# LasCon.net
KiCad netlist of a schematic drawn in EAGLE
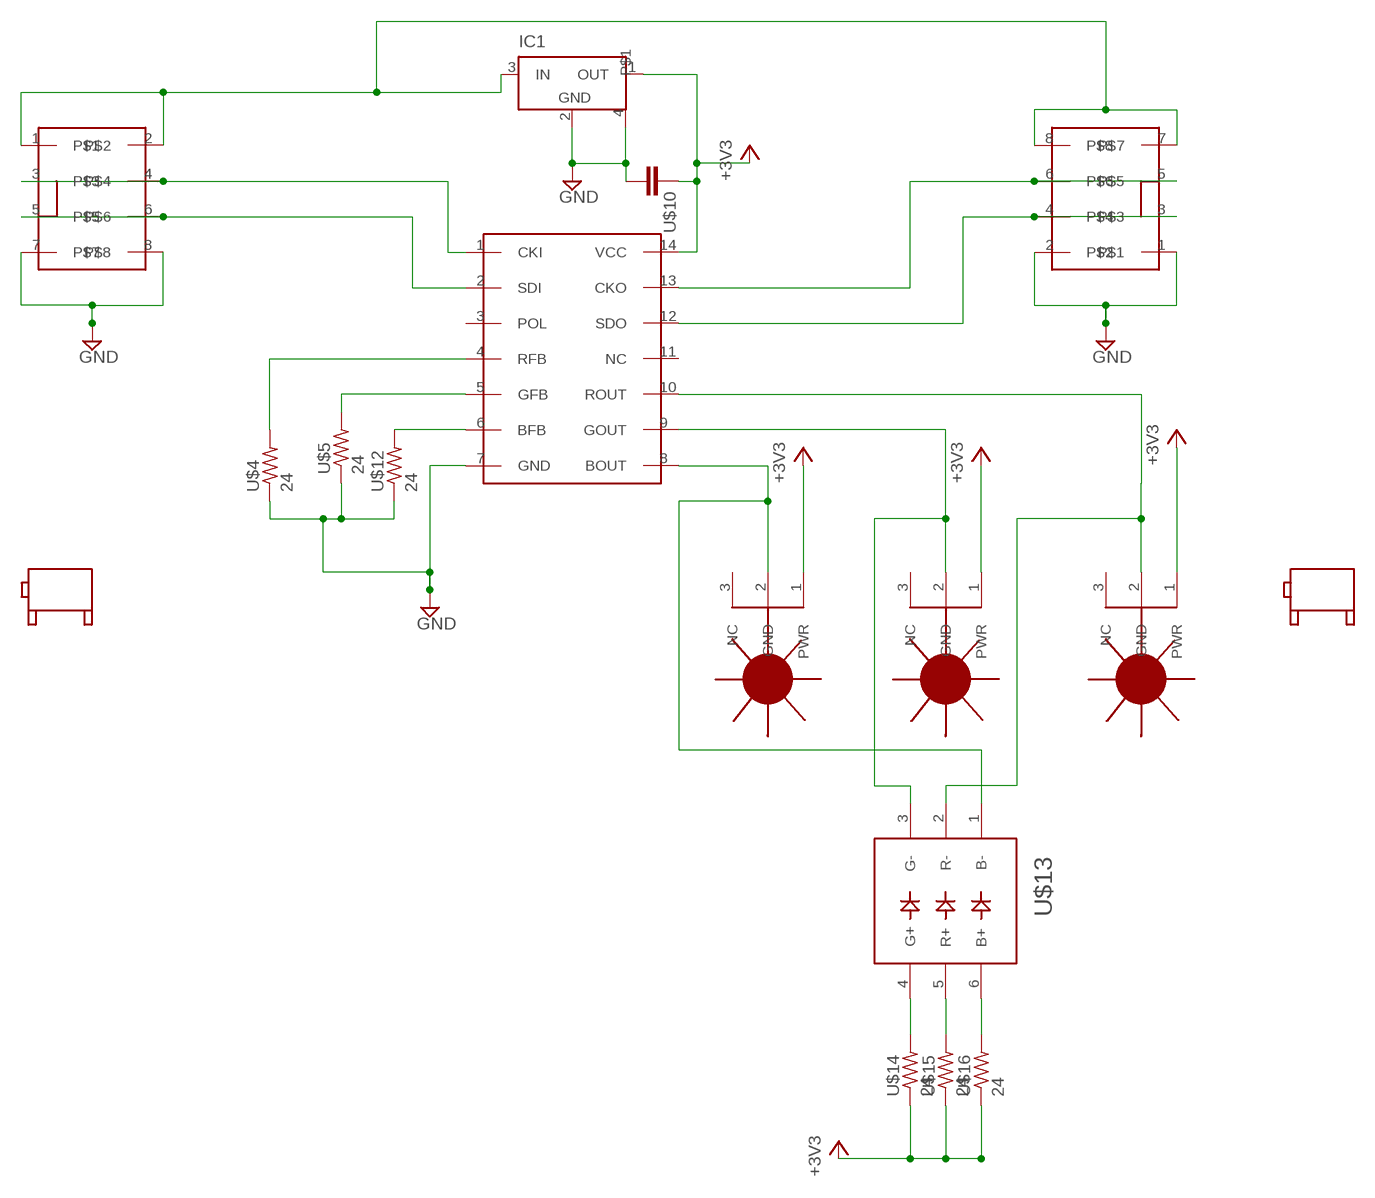
[diagram p0: schematic, sheet 1]

(export (version "E")
  (design (tool "Eeschema 10.0.6"))
  (components
    (comp (ref "IC1")
      (value "MCP1804T-3302I")
      (footprint "eagle-import:SOT223")
      (fields (field (name "MPN") "MCP1804T-3302I/DB"))
      (libsource (lib "eagle-import") (part "MCP1804T-3302I"))
    )
    (comp (ref "U$1")
      (value "2X4IDC")
      (footprint "eagle-import:2X04")
      (fields (field (name "MPN") "75869-132LF"))
      (libsource (lib "eagle-import") (part "2X4IDC"))
    )
    (comp (ref "U$2")
      (value "2X4IDC")
      (footprint "eagle-import:2X04")
      (fields (field (name "MPN") "75869-132LF"))
      (libsource (lib "eagle-import") (part "2X4IDC"))
    )
    (comp (ref "U$3")
      (value "WS2801")
      (footprint "eagle-import:SO14")
      (libsource (lib "eagle-import") (part "WS2801"))
    )
    (comp (ref "U$4")
      (value "24")
      (footprint "eagle-import:RF-C0805")
      (libsource (lib "eagle-import") (part "RF-R0805"))
    )
    (comp (ref "U$5")
      (value "24")
      (footprint "eagle-import:RF-C0805")
      (libsource (lib "eagle-import") (part "RF-R0805"))
    )
    (comp (ref "U$6")
      (value "LASER")
      (footprint "eagle-import:LASER")
      (libsource (lib "eagle-import") (part "LASER"))
    )
    (comp (ref "U$7")
      (value "LASER")
      (footprint "eagle-import:LASER")
      (libsource (lib "eagle-import") (part "LASER"))
    )
    (comp (ref "U$8")
      (value "90DEGMNT")
      (footprint "eagle-import:90DEGMNT")
      (libsource (lib "eagle-import") (part "90DEGMNT"))
    )
    (comp (ref "U$9")
      (value "90DEGMNT")
      (footprint "eagle-import:90DEGMNT")
      (libsource (lib "eagle-import") (part "90DEGMNT"))
    )
    (comp (ref "U$10")
      (value "RF-C0805")
      (footprint "eagle-import:C0805")
      (libsource (lib "eagle-import") (part "RF-C0805"))
    )
    (comp (ref "U$11")
      (value "LASER")
      (footprint "eagle-import:LASER")
      (libsource (lib "eagle-import") (part "LASER"))
    )
    (comp (ref "U$12")
      (value "24")
      (footprint "eagle-import:RF-C0805")
      (libsource (lib "eagle-import") (part "RF-R0805"))
    )
    (comp (ref "U$13")
      (value "LED5060A")
      (footprint "eagle-import:PLCC-6")
      (libsource (lib "eagle-import") (part "LED5060A"))
    )
    (comp (ref "U$14")
      (value "24")
      (footprint "eagle-import:RF-C0805")
      (libsource (lib "eagle-import") (part "RF-R0805"))
    )
    (comp (ref "U$15")
      (value "24")
      (footprint "eagle-import:RF-C0805")
      (libsource (lib "eagle-import") (part "RF-R0805"))
    )
    (comp (ref "U$16")
      (value "24")
      (footprint "eagle-import:RF-C0805")
      (libsource (lib "eagle-import") (part "RF-R0805"))
    )
  )
  (nets
    (net (code "1") (name "+3V3") (class "Default")
      (node (ref "IC1") (pin "1") (pinfunction "OUT_1") (pintype "output"))
      (node (ref "U$10") (pin "1") (pinfunction "1_1") (pintype "passive"))
      (node (ref "U$11") (pin "1") (pinfunction "PWR_1") (pintype "bidirectional"))
      (node (ref "U$14") (pin "1") (pinfunction "1_1") (pintype "passive"))
      (node (ref "U$15") (pin "1") (pinfunction "1_1") (pintype "passive"))
      (node (ref "U$16") (pin "1") (pinfunction "1_1") (pintype "passive"))
      (node (ref "U$3") (pin "14") (pinfunction "VCC_14") (pintype "bidirectional"))
      (node (ref "U$6") (pin "1") (pinfunction "PWR_1") (pintype "bidirectional"))
      (node (ref "U$7") (pin "1") (pinfunction "PWR_1") (pintype "bidirectional"))
    )
    (net (code "2") (name "GND") (class "Default")
      (node (ref "IC1") (pin "2") (pinfunction "GND_2") (pintype "power_in"))
      (node (ref "IC1") (pin "4") (pinfunction "P$1_4") (pintype "bidirectional"))
      (node (ref "U$1") (pin "7") (pinfunction "P$7_7") (pintype "bidirectional"))
      (node (ref "U$1") (pin "8") (pinfunction "P$8_8") (pintype "bidirectional"))
      (node (ref "U$10") (pin "2") (pinfunction "2_2") (pintype "passive"))
      (node (ref "U$12") (pin "1") (pinfunction "1_1") (pintype "passive"))
      (node (ref "U$2") (pin "1") (pinfunction "P$1_1") (pintype "bidirectional"))
      (node (ref "U$2") (pin "2") (pinfunction "P$2_2") (pintype "bidirectional"))
      (node (ref "U$3") (pin "7") (pinfunction "GND_7") (pintype "bidirectional"))
      (node (ref "U$4") (pin "1") (pinfunction "1_1") (pintype "passive"))
      (node (ref "U$5") (pin "1") (pinfunction "1_1") (pintype "passive"))
    )
    (net (code "3") (name "Net-(IC1-IN)") (class "Default")
      (node (ref "IC1") (pin "3") (pinfunction "IN_3") (pintype "input"))
      (node (ref "U$1") (pin "1") (pinfunction "P$1_1") (pintype "bidirectional"))
      (node (ref "U$1") (pin "2") (pinfunction "P$2_2") (pintype "bidirectional"))
      (node (ref "U$2") (pin "7") (pinfunction "P$7_7") (pintype "bidirectional"))
      (node (ref "U$2") (pin "8") (pinfunction "P$8_8") (pintype "bidirectional"))
    )
    (net (code "4") (name "Net-(U$1-P$3)") (class "Default")
      (node (ref "U$1") (pin "3") (pinfunction "P$3_3") (pintype "bidirectional"))
      (node (ref "U$1") (pin "4") (pinfunction "P$4_4") (pintype "bidirectional"))
      (node (ref "U$3") (pin "1") (pinfunction "CKI_1") (pintype "bidirectional"))
    )
    (net (code "5") (name "Net-(U$1-P$5)") (class "Default")
      (node (ref "U$1") (pin "5") (pinfunction "P$5_5") (pintype "bidirectional"))
      (node (ref "U$1") (pin "6") (pinfunction "P$6_6") (pintype "bidirectional"))
      (node (ref "U$3") (pin "2") (pinfunction "SDI_2") (pintype "bidirectional"))
    )
    (net (code "6") (name "Net-(U$2-P$3)") (class "Default")
      (node (ref "U$2") (pin "3") (pinfunction "P$3_3") (pintype "bidirectional"))
      (node (ref "U$2") (pin "4") (pinfunction "P$4_4") (pintype "bidirectional"))
      (node (ref "U$3") (pin "12") (pinfunction "SDO_12") (pintype "bidirectional"))
    )
    (net (code "7") (name "Net-(U$2-P$5)") (class "Default")
      (node (ref "U$2") (pin "5") (pinfunction "P$5_5") (pintype "bidirectional"))
      (node (ref "U$2") (pin "6") (pinfunction "P$6_6") (pintype "bidirectional"))
      (node (ref "U$3") (pin "13") (pinfunction "CKO_13") (pintype "bidirectional"))
    )
    (net (code "8") (name "Net-(U$3-BFB)") (class "Default")
      (node (ref "U$12") (pin "2") (pinfunction "2_2") (pintype "passive"))
      (node (ref "U$3") (pin "6") (pinfunction "BFB_6") (pintype "bidirectional"))
    )
    (net (code "9") (name "Net-(U$3-GFB)") (class "Default")
      (node (ref "U$3") (pin "5") (pinfunction "GFB_5") (pintype "bidirectional"))
      (node (ref "U$5") (pin "2") (pinfunction "2_2") (pintype "passive"))
    )
    (net (code "10") (name "Net-(U$3-RFB)") (class "Default")
      (node (ref "U$3") (pin "4") (pinfunction "RFB_4") (pintype "bidirectional"))
      (node (ref "U$4") (pin "2") (pinfunction "2_2") (pintype "passive"))
    )
    (net (code "11") (name "Net-(U$11-GND)") (class "Default")
      (node (ref "U$11") (pin "2") (pinfunction "GND_2") (pintype "bidirectional"))
      (node (ref "U$13") (pin "1") (pinfunction "B-_1") (pintype "bidirectional"))
      (node (ref "U$3") (pin "8") (pinfunction "BOUT_8") (pintype "bidirectional"))
    )
    (net (code "12") (name "Net-(U$13-B+)") (class "Default")
      (node (ref "U$13") (pin "6") (pinfunction "B+_6") (pintype "bidirectional"))
      (node (ref "U$16") (pin "2") (pinfunction "2_2") (pintype "passive"))
    )
    (net (code "13") (name "Net-(U$13-G+)") (class "Default")
      (node (ref "U$13") (pin "4") (pinfunction "G+_4") (pintype "bidirectional"))
      (node (ref "U$14") (pin "2") (pinfunction "2_2") (pintype "passive"))
    )
    (net (code "14") (name "Net-(U$13-G-)") (class "Default")
      (node (ref "U$13") (pin "3") (pinfunction "G-_3") (pintype "bidirectional"))
      (node (ref "U$3") (pin "9") (pinfunction "GOUT_9") (pintype "bidirectional"))
      (node (ref "U$6") (pin "2") (pinfunction "GND_2") (pintype "bidirectional"))
    )
    (net (code "15") (name "Net-(U$13-R+)") (class "Default")
      (node (ref "U$13") (pin "5") (pinfunction "R+_5") (pintype "bidirectional"))
      (node (ref "U$15") (pin "2") (pinfunction "2_2") (pintype "passive"))
    )
    (net (code "16") (name "Net-(U$13-R-)") (class "Default")
      (node (ref "U$13") (pin "2") (pinfunction "R-_2") (pintype "bidirectional"))
      (node (ref "U$3") (pin "10") (pinfunction "ROUT_10") (pintype "bidirectional"))
      (node (ref "U$7") (pin "2") (pinfunction "GND_2") (pintype "bidirectional"))
    )
    (net (code "17") (name "unconnected-(U$3-NC-Pad11)") (class "Default")
      (node (ref "U$3") (pin "11") (pinfunction "NC_11") (pintype "bidirectional"))
    )
    (net (code "18") (name "unconnected-(U$3-POL-Pad3)") (class "Default")
      (node (ref "U$3") (pin "3") (pinfunction "POL_3") (pintype "bidirectional"))
    )
    (net (code "19") (name "unconnected-(U$6-NC-Pad3)") (class "Default")
      (node (ref "U$6") (pin "3") (pinfunction "NC_3") (pintype "bidirectional"))
    )
    (net (code "20") (name "unconnected-(U$7-NC-Pad3)") (class "Default")
      (node (ref "U$7") (pin "3") (pinfunction "NC_3") (pintype "bidirectional"))
    )
    (net (code "21") (name "unconnected-(U$11-NC-Pad3)") (class "Default")
      (node (ref "U$11") (pin "3") (pinfunction "NC_3") (pintype "bidirectional"))
    )
  )
)
